# DDR3.net
KiCad netlist of a schematic drawn in Altium Designer
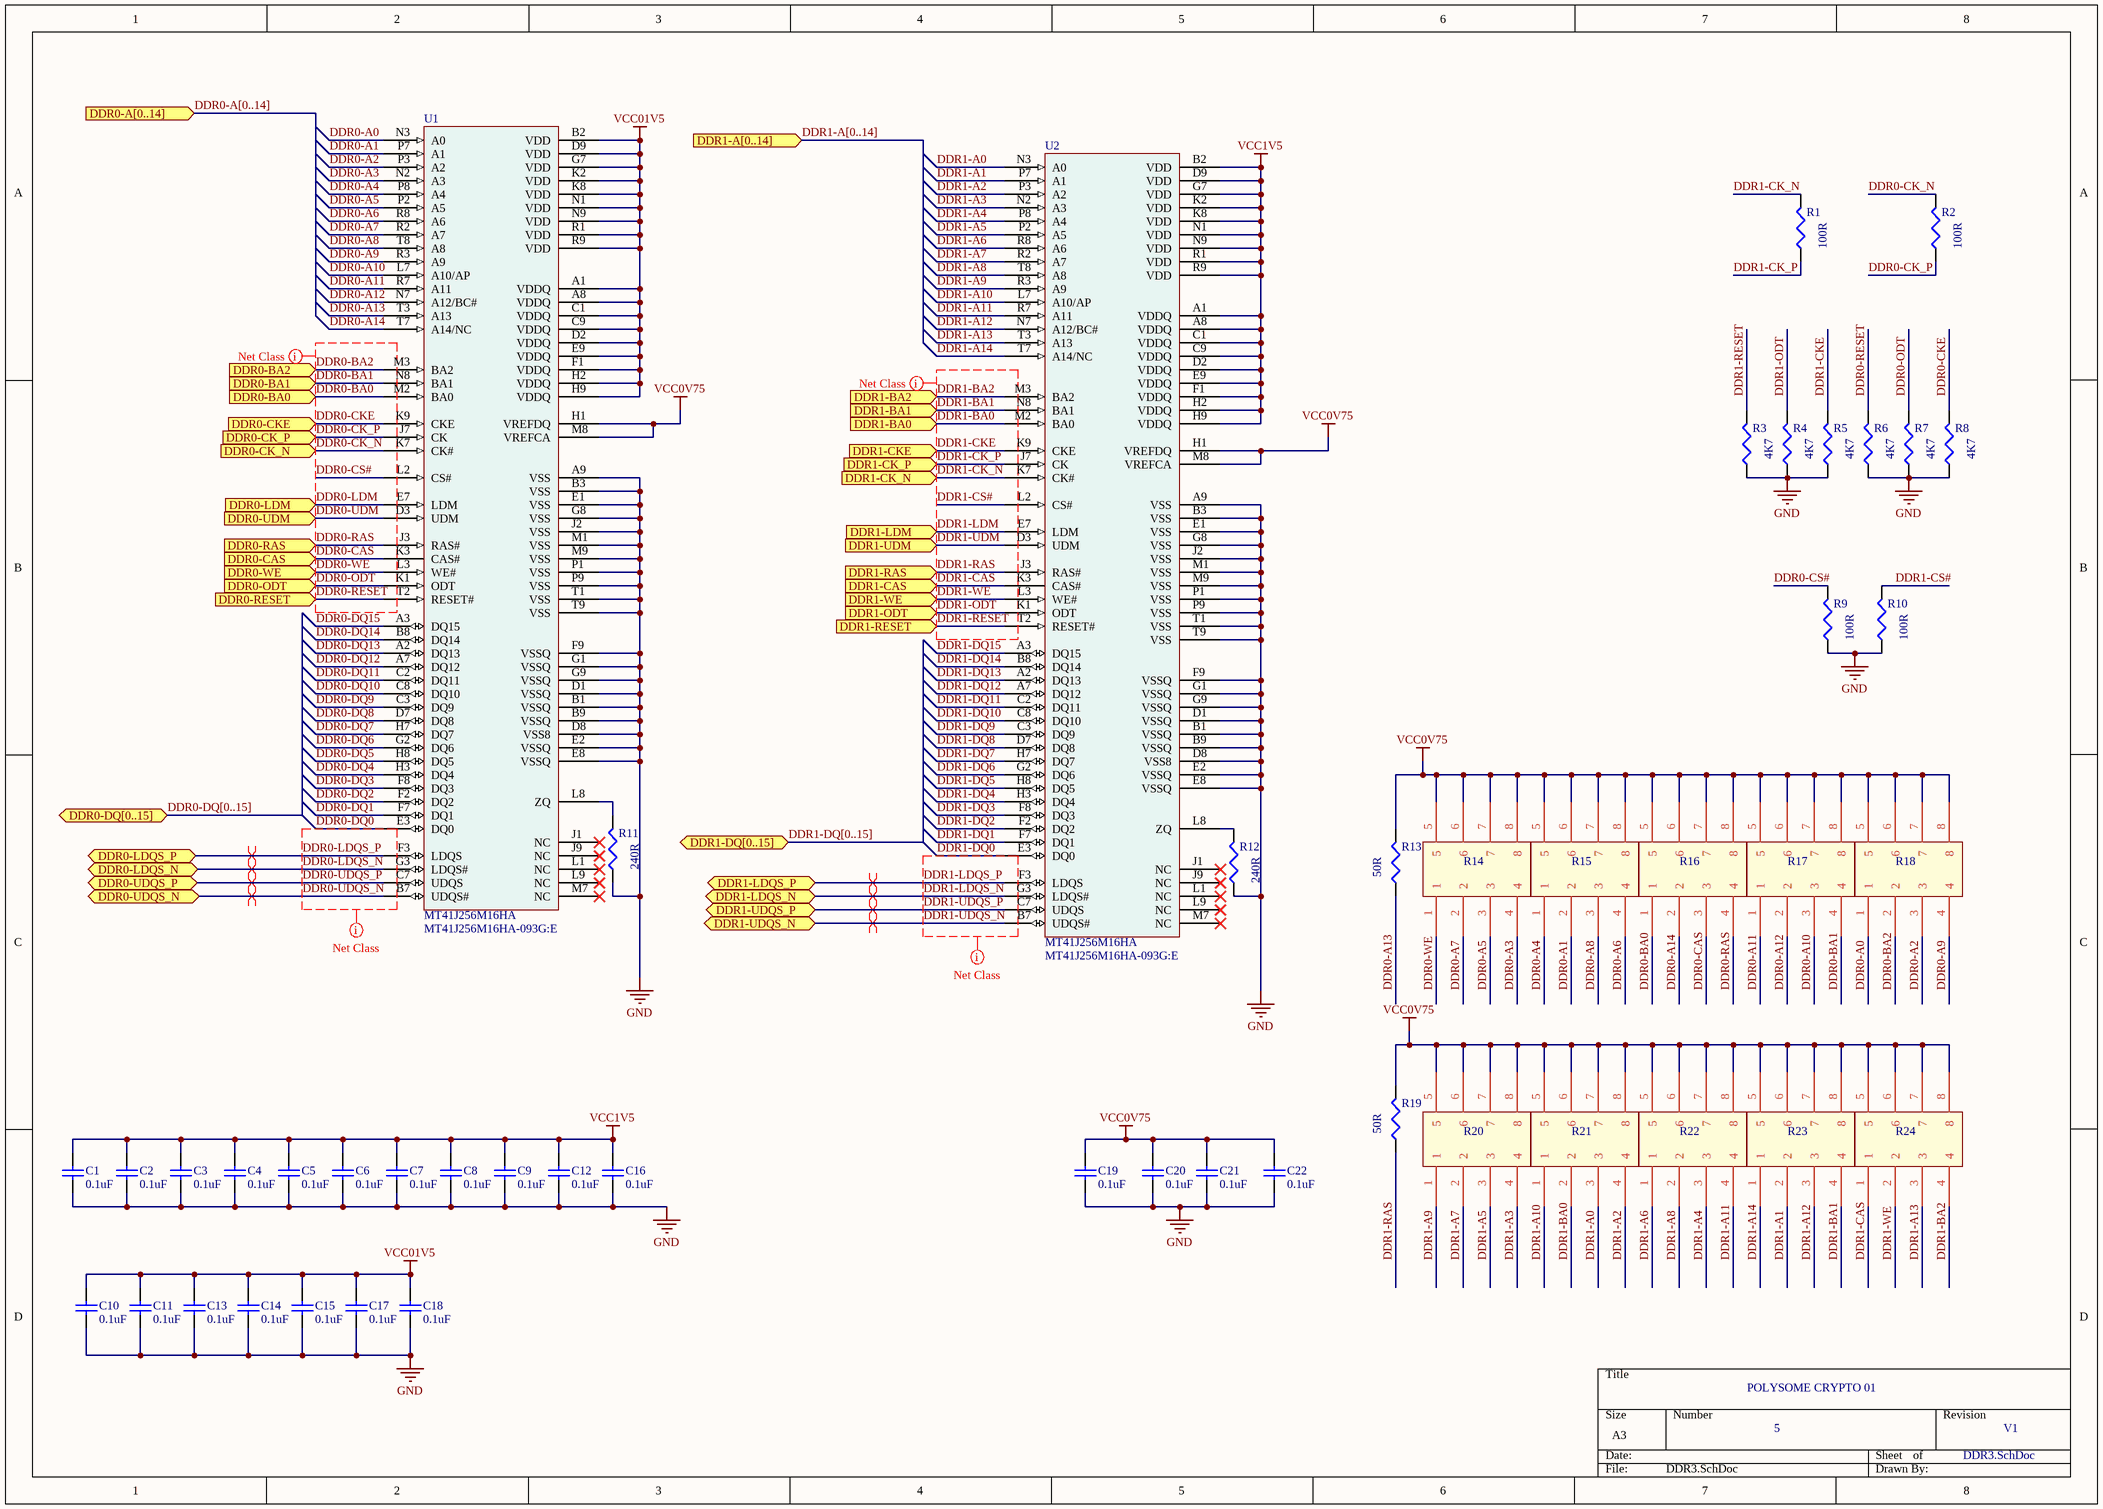
[diagram p0: DDR3.SchDoc]

(export (version "E")
  (design (tool "Eeschema 10.0.6"))
  (components
    (comp (ref "C1")
      (value "0.1uF")
      (footprint "0402")
      (description "Capacitor (Semiconductor SIM Model)")
      (fields (field (name "Comment") "Cap Semi") (field (name "PUBLISHER") "Altium Limited"))
      (libsource (lib "Miscellaneous Devices") (part "Cap Semi"))
    )
    (comp (ref "C2")
      (value "0.1uF")
      (footprint "0402")
      (description "Capacitor (Semiconductor SIM Model)")
      (fields (field (name "Comment") "Cap Semi") (field (name "PUBLISHER") "Altium Limited"))
      (libsource (lib "Miscellaneous Devices") (part "Cap Semi"))
    )
    (comp (ref "C3")
      (value "0.1uF")
      (footprint "0402")
      (description "Capacitor (Semiconductor SIM Model)")
      (fields (field (name "Comment") "Cap Semi") (field (name "PUBLISHER") "Altium Limited"))
      (libsource (lib "Miscellaneous Devices") (part "Cap Semi"))
    )
    (comp (ref "C4")
      (value "0.1uF")
      (footprint "0402")
      (description "Capacitor (Semiconductor SIM Model)")
      (fields (field (name "Comment") "Cap Semi") (field (name "PUBLISHER") "Altium Limited"))
      (libsource (lib "Miscellaneous Devices") (part "Cap Semi"))
    )
    (comp (ref "C5")
      (value "0.1uF")
      (footprint "0402")
      (description "Capacitor (Semiconductor SIM Model)")
      (fields (field (name "Comment") "Cap Semi") (field (name "PUBLISHER") "Altium Limited"))
      (libsource (lib "Miscellaneous Devices") (part "Cap Semi"))
    )
    (comp (ref "C6")
      (value "0.1uF")
      (footprint "0402")
      (description "Capacitor (Semiconductor SIM Model)")
      (fields (field (name "Comment") "Cap Semi") (field (name "PUBLISHER") "Altium Limited"))
      (libsource (lib "Miscellaneous Devices") (part "Cap Semi"))
    )
    (comp (ref "C7")
      (value "0.1uF")
      (footprint "0402")
      (description "Capacitor (Semiconductor SIM Model)")
      (fields (field (name "Comment") "Cap Semi") (field (name "PUBLISHER") "Altium Limited"))
      (libsource (lib "Miscellaneous Devices") (part "Cap Semi"))
    )
    (comp (ref "C8")
      (value "0.1uF")
      (footprint "0402")
      (description "Capacitor (Semiconductor SIM Model)")
      (fields (field (name "Comment") "Cap Semi") (field (name "PUBLISHER") "Altium Limited"))
      (libsource (lib "Miscellaneous Devices") (part "Cap Semi"))
    )
    (comp (ref "C9")
      (value "0.1uF")
      (footprint "0402")
      (description "Capacitor (Semiconductor SIM Model)")
      (fields (field (name "Comment") "Cap Semi") (field (name "PUBLISHER") "Altium Limited"))
      (libsource (lib "Miscellaneous Devices") (part "Cap Semi"))
    )
    (comp (ref "C10")
      (value "0.1uF")
      (footprint "0402")
      (description "Capacitor (Semiconductor SIM Model)")
      (fields (field (name "Comment") "Cap Semi") (field (name "PUBLISHER") "Altium Limited"))
      (libsource (lib "Miscellaneous Devices") (part "Cap Semi"))
    )
    (comp (ref "C11")
      (value "0.1uF")
      (footprint "0402")
      (description "Capacitor (Semiconductor SIM Model)")
      (fields (field (name "Comment") "Cap Semi") (field (name "PUBLISHER") "Altium Limited"))
      (libsource (lib "Miscellaneous Devices") (part "Cap Semi"))
    )
    (comp (ref "C12")
      (value "0.1uF")
      (footprint "0402")
      (description "Capacitor (Semiconductor SIM Model)")
      (fields (field (name "Comment") "Cap Semi") (field (name "PUBLISHER") "Altium Limited"))
      (libsource (lib "Miscellaneous Devices") (part "Cap Semi"))
    )
    (comp (ref "C13")
      (value "0.1uF")
      (footprint "0402")
      (description "Capacitor (Semiconductor SIM Model)")
      (fields (field (name "Comment") "Cap Semi") (field (name "PUBLISHER") "Altium Limited"))
      (libsource (lib "Miscellaneous Devices") (part "Cap Semi"))
    )
    (comp (ref "C14")
      (value "0.1uF")
      (footprint "0402")
      (description "Capacitor (Semiconductor SIM Model)")
      (fields (field (name "Comment") "Cap Semi") (field (name "PUBLISHER") "Altium Limited"))
      (libsource (lib "Miscellaneous Devices") (part "Cap Semi"))
    )
    (comp (ref "C15")
      (value "0.1uF")
      (footprint "0402")
      (description "Capacitor (Semiconductor SIM Model)")
      (fields (field (name "Comment") "Cap Semi") (field (name "PUBLISHER") "Altium Limited"))
      (libsource (lib "Miscellaneous Devices") (part "Cap Semi"))
    )
    (comp (ref "C16")
      (value "0.1uF")
      (footprint "0402")
      (description "Capacitor (Semiconductor SIM Model)")
      (fields (field (name "Comment") "Cap Semi") (field (name "PUBLISHER") "Altium Limited"))
      (libsource (lib "Miscellaneous Devices") (part "Cap Semi"))
    )
    (comp (ref "C17")
      (value "0.1uF")
      (footprint "0402")
      (description "Capacitor (Semiconductor SIM Model)")
      (fields (field (name "Comment") "Cap Semi") (field (name "PUBLISHER") "Altium Limited"))
      (libsource (lib "Miscellaneous Devices") (part "Cap Semi"))
    )
    (comp (ref "C18")
      (value "0.1uF")
      (footprint "0402")
      (description "Capacitor (Semiconductor SIM Model)")
      (fields (field (name "Comment") "Cap Semi") (field (name "PUBLISHER") "Altium Limited"))
      (libsource (lib "Miscellaneous Devices") (part "Cap Semi"))
    )
    (comp (ref "C19")
      (value "0.1uF")
      (footprint "0402")
      (description "Capacitor (Semiconductor SIM Model)")
      (fields (field (name "Comment") "Cap Semi") (field (name "PUBLISHER") "Altium Limited"))
      (libsource (lib "Miscellaneous Devices") (part "Cap Semi"))
    )
    (comp (ref "C20")
      (value "0.1uF")
      (footprint "0402")
      (description "Capacitor (Semiconductor SIM Model)")
      (fields (field (name "Comment") "Cap Semi") (field (name "PUBLISHER") "Altium Limited"))
      (libsource (lib "Miscellaneous Devices") (part "Cap Semi"))
    )
    (comp (ref "C21")
      (value "0.1uF")
      (footprint "0402")
      (description "Capacitor (Semiconductor SIM Model)")
      (fields (field (name "Comment") "Cap Semi") (field (name "PUBLISHER") "Altium Limited"))
      (libsource (lib "Miscellaneous Devices") (part "Cap Semi"))
    )
    (comp (ref "C22")
      (value "0.1uF")
      (footprint "0402")
      (description "Capacitor (Semiconductor SIM Model)")
      (fields (field (name "Comment") "Cap Semi") (field (name "PUBLISHER") "Altium Limited"))
      (libsource (lib "Miscellaneous Devices") (part "Cap Semi"))
    )
    (comp (ref "R1")
      (value "100R")
      (footprint "0402")
      (description "Resistor")
      (fields (field (name "Comment") "Res3") (field (name "PUBLISHER") "Altium Limited"))
      (libsource (lib "Miscellaneous Devices") (part "Res3"))
    )
    (comp (ref "R2")
      (value "100R")
      (footprint "0402")
      (description "Resistor")
      (fields (field (name "Comment") "Res3") (field (name "PUBLISHER") "Altium Limited"))
      (libsource (lib "Miscellaneous Devices") (part "Res3"))
    )
    (comp (ref "R3")
      (value "4K7")
      (footprint "0402")
      (description "Resistor")
      (fields (field (name "Comment") "Res3") (field (name "PUBLISHER") "Altium Limited"))
      (libsource (lib "Miscellaneous Devices") (part "Res3"))
    )
    (comp (ref "R4")
      (value "4K7")
      (footprint "0402")
      (description "Resistor")
      (fields (field (name "Comment") "Res3") (field (name "PUBLISHER") "Altium Limited"))
      (libsource (lib "Miscellaneous Devices") (part "Res3"))
    )
    (comp (ref "R5")
      (value "4K7")
      (footprint "0402")
      (description "Resistor")
      (fields (field (name "Comment") "Res3") (field (name "PUBLISHER") "Altium Limited"))
      (libsource (lib "Miscellaneous Devices") (part "Res3"))
    )
    (comp (ref "R6")
      (value "4K7")
      (footprint "0402")
      (description "Resistor")
      (fields (field (name "Comment") "Res3") (field (name "PUBLISHER") "Altium Limited"))
      (libsource (lib "Miscellaneous Devices") (part "Res3"))
    )
    (comp (ref "R7")
      (value "4K7")
      (footprint "0402")
      (description "Resistor")
      (fields (field (name "Comment") "Res3") (field (name "PUBLISHER") "Altium Limited"))
      (libsource (lib "Miscellaneous Devices") (part "Res3"))
    )
    (comp (ref "R8")
      (value "4K7")
      (footprint "0402")
      (description "Resistor")
      (fields (field (name "Comment") "Res3") (field (name "PUBLISHER") "Altium Limited"))
      (libsource (lib "Miscellaneous Devices") (part "Res3"))
    )
    (comp (ref "R9")
      (value "100R")
      (footprint "0402")
      (description "Resistor")
      (fields (field (name "Comment") "Res3") (field (name "PUBLISHER") "Altium Limited"))
      (libsource (lib "Miscellaneous Devices") (part "Res3"))
    )
    (comp (ref "R10")
      (value "100R")
      (footprint "0402")
      (description "Resistor")
      (fields (field (name "Comment") "Res3") (field (name "PUBLISHER") "Altium Limited"))
      (libsource (lib "Miscellaneous Devices") (part "Res3"))
    )
    (comp (ref "R11")
      (value "240R")
      (footprint "0402")
      (description "Resistor")
      (fields (field (name "Comment") "Res3") (field (name "PUBLISHER") "Altium Limited"))
      (libsource (lib "Miscellaneous Devices") (part "Res3"))
    )
    (comp (ref "R12")
      (value "240R")
      (footprint "0402")
      (description "Resistor")
      (fields (field (name "Comment") "Res3") (field (name "PUBLISHER") "Altium Limited"))
      (libsource (lib "Miscellaneous Devices") (part "Res3"))
    )
    (comp (ref "R13")
      (value "50R")
      (footprint "0402")
      (description "Resistor")
      (fields (field (name "Comment") "Res3") (field (name "PUBLISHER") "Altium Limited"))
      (libsource (lib "Miscellaneous Devices") (part "Res3"))
    )
    (comp (ref "R14")
      (value "RES_4_PACK")
      (footprint "YC124-FR-0749R9L")
      (description "Resistor Networks & Arrays 49.9 Ohm 1% 1/16W 50 Volts")
      (fields
        (field (name "MANUFACTURER") "Yageo")
        (field (name "MANUFACTURER PART NUMBER") "YC124-FR-0749R9L")
      )
      (libsource (lib "PolySomeCrypto01") (part "YC124-FR-0749R9L"))
    )
    (comp (ref "R15")
      (value "RES_4_PACK")
      (footprint "YC124-FR-0749R9L")
      (description "Resistor Networks & Arrays 49.9 Ohm 1% 1/16W 50 Volts")
      (fields
        (field (name "MANUFACTURER") "Yageo")
        (field (name "MANUFACTURER PART NUMBER") "YC124-FR-0749R9L")
      )
      (libsource (lib "PolySomeCrypto01") (part "YC124-FR-0749R9L"))
    )
    (comp (ref "R16")
      (value "RES_4_PACK")
      (footprint "YC124-FR-0749R9L")
      (description "Resistor Networks & Arrays 49.9 Ohm 1% 1/16W 50 Volts")
      (fields
        (field (name "MANUFACTURER") "Yageo")
        (field (name "MANUFACTURER PART NUMBER") "YC124-FR-0749R9L")
      )
      (libsource (lib "PolySomeCrypto01") (part "YC124-FR-0749R9L"))
    )
    (comp (ref "R17")
      (value "RES_4_PACK")
      (footprint "YC124-FR-0749R9L")
      (description "Resistor Networks & Arrays 49.9 Ohm 1% 1/16W 50 Volts")
      (fields
        (field (name "MANUFACTURER") "Yageo")
        (field (name "MANUFACTURER PART NUMBER") "YC124-FR-0749R9L")
      )
      (libsource (lib "PolySomeCrypto01") (part "YC124-FR-0749R9L"))
    )
    (comp (ref "R18")
      (value "RES_4_PACK")
      (footprint "YC124-FR-0749R9L")
      (description "Resistor Networks & Arrays 49.9 Ohm 1% 1/16W 50 Volts")
      (fields
        (field (name "MANUFACTURER") "Yageo")
        (field (name "MANUFACTURER PART NUMBER") "YC124-FR-0749R9L")
      )
      (libsource (lib "PolySomeCrypto01") (part "YC124-FR-0749R9L"))
    )
    (comp (ref "R19")
      (value "50R")
      (footprint "0402")
      (description "Resistor")
      (fields (field (name "Comment") "Res3") (field (name "PUBLISHER") "Altium Limited"))
      (libsource (lib "Miscellaneous Devices") (part "Res3"))
    )
    (comp (ref "R20")
      (value "RES_4_PACK")
      (footprint "YC124-FR-0749R9L")
      (description "Resistor Networks & Arrays 49.9 Ohm 1% 1/16W 50 Volts")
      (fields
        (field (name "MANUFACTURER") "Yageo")
        (field (name "MANUFACTURER PART NUMBER") "YC124-FR-0749R9L")
      )
      (libsource (lib "PolySomeCrypto01") (part "YC124-FR-0749R9L"))
    )
    (comp (ref "R21")
      (value "RES_4_PACK")
      (footprint "YC124-FR-0749R9L")
      (description "Resistor Networks & Arrays 49.9 Ohm 1% 1/16W 50 Volts")
      (fields
        (field (name "MANUFACTURER") "Yageo")
        (field (name "MANUFACTURER PART NUMBER") "YC124-FR-0749R9L")
      )
      (libsource (lib "PolySomeCrypto01") (part "YC124-FR-0749R9L"))
    )
    (comp (ref "R22")
      (value "RES_4_PACK")
      (footprint "YC124-FR-0749R9L")
      (description "Resistor Networks & Arrays 49.9 Ohm 1% 1/16W 50 Volts")
      (fields
        (field (name "MANUFACTURER") "Yageo")
        (field (name "MANUFACTURER PART NUMBER") "YC124-FR-0749R9L")
      )
      (libsource (lib "PolySomeCrypto01") (part "YC124-FR-0749R9L"))
    )
    (comp (ref "R23")
      (value "RES_4_PACK")
      (footprint "YC124-FR-0749R9L")
      (description "Resistor Networks & Arrays 49.9 Ohm 1% 1/16W 50 Volts")
      (fields
        (field (name "MANUFACTURER") "Yageo")
        (field (name "MANUFACTURER PART NUMBER") "YC124-FR-0749R9L")
      )
      (libsource (lib "PolySomeCrypto01") (part "YC124-FR-0749R9L"))
    )
    (comp (ref "R24")
      (value "RES_4_PACK")
      (footprint "YC124-FR-0749R9L")
      (description "Resistor Networks & Arrays 49.9 Ohm 1% 1/16W 50 Volts")
      (fields
        (field (name "MANUFACTURER") "Yageo")
        (field (name "MANUFACTURER PART NUMBER") "YC124-FR-0749R9L")
      )
      (libsource (lib "PolySomeCrypto01") (part "YC124-FR-0749R9L"))
    )
    (comp (ref "U1")
      (value "MT41J256M16HA")
      (description "IC DDR3 SDRAM 4GBIT FBGA")
      (fields
        (field (name "MANUFACTURER") "Micron Technology Inc")
        (field (name "MANUFACTURER PART NUMBER") "MT41J256M16HA-093G:E")
      )
      (libsource (lib "PolySomeCrypto01") (part "MT41J256M16HA-093G{colon}E"))
    )
    (comp (ref "U2")
      (value "MT41J256M16HA")
      (description "IC DDR3 SDRAM 4GBIT FBGA")
      (fields
        (field (name "MANUFACTURER") "Micron Technology Inc")
        (field (name "MANUFACTURER PART NUMBER") "MT41J256M16HA-093G:E")
      )
      (libsource (lib "PolySomeCrypto01") (part "MT41J256M16HA-093G{colon}E"))
    )
  )
  (nets
    (net (code "1") (name "/DDR0-A0") (class "Default")
      (node (ref "R18") (pin "1") (pinfunction "1_1") (pintype "passive"))
      (node (ref "U1") (pin "N3") (pinfunction "A0_N3") (pintype "input"))
    )
    (net (code "2") (name "/DDR0-A1") (class "Default")
      (node (ref "R15") (pin "2") (pinfunction "2_2") (pintype "passive"))
      (node (ref "U1") (pin "P7") (pinfunction "A1_P7") (pintype "input"))
    )
    (net (code "3") (name "/DDR0-A2") (class "Default")
      (node (ref "R18") (pin "3") (pinfunction "3_3") (pintype "passive"))
      (node (ref "U1") (pin "P3") (pinfunction "A2_P3") (pintype "input"))
    )
    (net (code "4") (name "/DDR0-A3") (class "Default")
      (node (ref "R14") (pin "4") (pinfunction "4_4") (pintype "passive"))
      (node (ref "U1") (pin "N2") (pinfunction "A3_N2") (pintype "input"))
    )
    (net (code "5") (name "/DDR0-A4") (class "Default")
      (node (ref "R15") (pin "1") (pinfunction "1_1") (pintype "passive"))
      (node (ref "U1") (pin "P8") (pinfunction "A4_P8") (pintype "input"))
    )
    (net (code "6") (name "/DDR0-A5") (class "Default")
      (node (ref "R14") (pin "3") (pinfunction "3_3") (pintype "passive"))
      (node (ref "U1") (pin "P2") (pinfunction "A5_P2") (pintype "input"))
    )
    (net (code "7") (name "/DDR0-A6") (class "Default")
      (node (ref "R15") (pin "4") (pinfunction "4_4") (pintype "passive"))
      (node (ref "U1") (pin "R8") (pinfunction "A6_R8") (pintype "input"))
    )
    (net (code "8") (name "/DDR0-A7") (class "Default")
      (node (ref "R14") (pin "2") (pinfunction "2_2") (pintype "passive"))
      (node (ref "U1") (pin "R2") (pinfunction "A7_R2") (pintype "input"))
    )
    (net (code "9") (name "/DDR0-A8") (class "Default")
      (node (ref "R15") (pin "3") (pinfunction "3_3") (pintype "passive"))
      (node (ref "U1") (pin "T8") (pinfunction "A8_T8") (pintype "input"))
    )
    (net (code "10") (name "/DDR0-A9") (class "Default")
      (node (ref "R18") (pin "4") (pinfunction "4_4") (pintype "passive"))
      (node (ref "U1") (pin "R3") (pinfunction "A9_R3") (pintype "input"))
    )
    (net (code "11") (name "/DDR0-A10") (class "Default")
      (node (ref "R17") (pin "3") (pinfunction "3_3") (pintype "passive"))
      (node (ref "U1") (pin "L7") (pinfunction "A10/AP_L7") (pintype "input"))
    )
    (net (code "12") (name "/DDR0-A11") (class "Default")
      (node (ref "R17") (pin "1") (pinfunction "1_1") (pintype "passive"))
      (node (ref "U1") (pin "R7") (pinfunction "A11_R7") (pintype "input"))
    )
    (net (code "13") (name "/DDR0-A12") (class "Default")
      (node (ref "R17") (pin "2") (pinfunction "2_2") (pintype "passive"))
      (node (ref "U1") (pin "N7") (pinfunction "A12/BC#_N7") (pintype "input"))
    )
    (net (code "14") (name "/DDR0-A13") (class "Default")
      (node (ref "R13") (pin "1") (pinfunction "1_1") (pintype "passive"))
      (node (ref "U1") (pin "T3") (pinfunction "A13_T3") (pintype "input"))
    )
    (net (code "15") (name "/DDR0-A14") (class "Default")
      (node (ref "R16") (pin "2") (pinfunction "2_2") (pintype "passive"))
      (node (ref "U1") (pin "T7") (pinfunction "A14/NC_T7") (pintype "input"))
    )
    (net (code "17") (name "/DDR0-BA0") (class "Default")
      (node (ref "R16") (pin "1") (pinfunction "1_1") (pintype "passive"))
      (node (ref "U1") (pin "M2") (pinfunction "BA0_M2") (pintype "input"))
    )
    (net (code "18") (name "/DDR0-BA1") (class "Default")
      (node (ref "R17") (pin "4") (pinfunction "4_4") (pintype "passive"))
      (node (ref "U1") (pin "N8") (pinfunction "BA1_N8") (pintype "input"))
    )
    (net (code "19") (name "/DDR0-BA2") (class "Default")
      (node (ref "R18") (pin "2") (pinfunction "2_2") (pintype "passive"))
      (node (ref "U1") (pin "M3") (pinfunction "BA2_M3") (pintype "input"))
    )
    (net (code "20") (name "/DDR0-CAS") (class "Default")
      (node (ref "R16") (pin "3") (pinfunction "3_3") (pintype "passive"))
      (node (ref "U1") (pin "K3") (pinfunction "CAS#_K3") (pintype "passive"))
    )
    (net (code "21") (name "/DDR0-CKE") (class "Default")
      (node (ref "R8") (pin "2") (pinfunction "2_2") (pintype "passive"))
      (node (ref "U1") (pin "K9") (pinfunction "CKE_K9") (pintype "input"))
    )
    (net (code "22") (name "/DDR0-CK_N") (class "Default")
      (node (ref "R2") (pin "2") (pinfunction "2_2") (pintype "passive"))
      (node (ref "U1") (pin "K7") (pinfunction "CK#_K7") (pintype "input"))
    )
    (net (code "23") (name "/DDR0-CK_P") (class "Default")
      (node (ref "R2") (pin "1") (pinfunction "1_1") (pintype "passive"))
      (node (ref "U1") (pin "J7") (pinfunction "CK_J7") (pintype "input"))
    )
    (net (code "24") (name "/DDR0-CS#") (class "Default")
      (node (ref "R9") (pin "2") (pinfunction "2_2") (pintype "passive"))
      (node (ref "U1") (pin "L2") (pinfunction "CS#_L2") (pintype "input"))
    )
    (net (code "25") (name "/DDR0-DQ0") (class "Default")
      (node (ref "U1") (pin "E3") (pinfunction "DQ0_E3") (pintype "bidirectional"))
    )
    (net (code "26") (name "/DDR0-DQ1") (class "Default")
      (node (ref "U1") (pin "F7") (pinfunction "DQ1_F7") (pintype "bidirectional"))
    )
    (net (code "27") (name "/DDR0-DQ2") (class "Default")
      (node (ref "U1") (pin "F2") (pinfunction "DQ2_F2") (pintype "bidirectional"))
    )
    (net (code "28") (name "/DDR0-DQ3") (class "Default")
      (node (ref "U1") (pin "F8") (pinfunction "DQ3_F8") (pintype "bidirectional"))
    )
    (net (code "29") (name "/DDR0-DQ4") (class "Default")
      (node (ref "U1") (pin "H3") (pinfunction "DQ4_H3") (pintype "bidirectional"))
    )
    (net (code "30") (name "/DDR0-DQ5") (class "Default")
      (node (ref "U1") (pin "H8") (pinfunction "DQ5_H8") (pintype "bidirectional"))
    )
    (net (code "31") (name "/DDR0-DQ6") (class "Default")
      (node (ref "U1") (pin "G2") (pinfunction "DQ6_G2") (pintype "bidirectional"))
    )
    (net (code "32") (name "/DDR0-DQ7") (class "Default")
      (node (ref "U1") (pin "H7") (pinfunction "DQ7_H7") (pintype "bidirectional"))
    )
    (net (code "33") (name "/DDR0-DQ8") (class "Default")
      (node (ref "U1") (pin "D7") (pinfunction "DQ8_D7") (pintype "bidirectional"))
    )
    (net (code "34") (name "/DDR0-DQ9") (class "Default")
      (node (ref "U1") (pin "C3") (pinfunction "DQ9_C3") (pintype "bidirectional"))
    )
    (net (code "35") (name "/DDR0-DQ10") (class "Default")
      (node (ref "U1") (pin "C8") (pinfunction "DQ10_C8") (pintype "bidirectional"))
    )
    (net (code "36") (name "/DDR0-DQ11") (class "Default")
      (node (ref "U1") (pin "C2") (pinfunction "DQ11_C2") (pintype "bidirectional"))
    )
    (net (code "37") (name "/DDR0-DQ12") (class "Default")
      (node (ref "U1") (pin "A7") (pinfunction "DQ12_A7") (pintype "bidirectional"))
    )
    (net (code "38") (name "/DDR0-DQ13") (class "Default")
      (node (ref "U1") (pin "A2") (pinfunction "DQ13_A2") (pintype "bidirectional"))
    )
    (net (code "39") (name "/DDR0-DQ14") (class "Default")
      (node (ref "U1") (pin "B8") (pinfunction "DQ14_B8") (pintype "bidirectional"))
    )
    (net (code "40") (name "/DDR0-DQ15") (class "Default")
      (node (ref "U1") (pin "A3") (pinfunction "DQ15_A3") (pintype "bidirectional"))
    )
    (net (code "42") (name "/DDR0-LDM") (class "Default")
      (node (ref "U1") (pin "E7") (pinfunction "LDM_E7") (pintype "input"))
    )
    (net (code "43") (name "/DDR0-LDQS_N") (class "Default")
      (node (ref "U1") (pin "G3") (pinfunction "LDQS#_G3") (pintype "bidirectional"))
    )
    (net (code "44") (name "/DDR0-LDQS_P") (class "Default")
      (node (ref "U1") (pin "F3") (pinfunction "LDQS_F3") (pintype "bidirectional"))
    )
    (net (code "45") (name "/DDR0-ODT") (class "Default")
      (node (ref "R7") (pin "2") (pinfunction "2_2") (pintype "passive"))
      (node (ref "U1") (pin "K1") (pinfunction "ODT_K1") (pintype "input"))
    )
    (net (code "46") (name "/DDR0-RAS") (class "Default")
      (node (ref "R16") (pin "4") (pinfunction "4_4") (pintype "passive"))
      (node (ref "U1") (pin "J3") (pinfunction "RAS#_J3") (pintype "input"))
    )
    (net (code "47") (name "/DDR0-RESET") (class "Default")
      (node (ref "R6") (pin "2") (pinfunction "2_2") (pintype "passive"))
      (node (ref "U1") (pin "T2") (pinfunction "RESET#_T2") (pintype "input"))
    )
    (net (code "48") (name "/DDR0-UDM") (class "Default")
      (node (ref "U1") (pin "D3") (pinfunction "UDM_D3") (pintype "input"))
    )
    (net (code "49") (name "/DDR0-UDQS_N") (class "Default")
      (node (ref "U1") (pin "B7") (pinfunction "UDQS#_B7") (pintype "bidirectional"))
    )
    (net (code "50") (name "/DDR0-UDQS_P") (class "Default")
      (node (ref "U1") (pin "C7") (pinfunction "UDQS_C7") (pintype "bidirectional"))
    )
    (net (code "51") (name "/DDR0-WE") (class "Default")
      (node (ref "R14") (pin "1") (pinfunction "1_1") (pintype "passive"))
      (node (ref "U1") (pin "L3") (pinfunction "WE#_L3") (pintype "input"))
    )
    (net (code "52") (name "/DDR1-A0") (class "Default")
      (node (ref "R21") (pin "3") (pinfunction "3_3") (pintype "passive"))
      (node (ref "U2") (pin "N3") (pinfunction "A0_N3") (pintype "input"))
    )
    (net (code "53") (name "/DDR1-A1") (class "Default")
      (node (ref "R23") (pin "2") (pinfunction "2_2") (pintype "passive"))
      (node (ref "U2") (pin "P7") (pinfunction "A1_P7") (pintype "input"))
    )
    (net (code "54") (name "/DDR1-A2") (class "Default")
      (node (ref "R21") (pin "4") (pinfunction "4_4") (pintype "passive"))
      (node (ref "U2") (pin "P3") (pinfunction "A2_P3") (pintype "input"))
    )
    (net (code "55") (name "/DDR1-A3") (class "Default")
      (node (ref "R20") (pin "4") (pinfunction "4_4") (pintype "passive"))
      (node (ref "U2") (pin "N2") (pinfunction "A3_N2") (pintype "input"))
    )
    (net (code "56") (name "/DDR1-A4") (class "Default")
      (node (ref "R22") (pin "3") (pinfunction "3_3") (pintype "passive"))
      (node (ref "U2") (pin "P8") (pinfunction "A4_P8") (pintype "input"))
    )
    (net (code "57") (name "/DDR1-A5") (class "Default")
      (node (ref "R20") (pin "3") (pinfunction "3_3") (pintype "passive"))
      (node (ref "U2") (pin "P2") (pinfunction "A5_P2") (pintype "input"))
    )
    (net (code "58") (name "/DDR1-A6") (class "Default")
      (node (ref "R22") (pin "1") (pinfunction "1_1") (pintype "passive"))
      (node (ref "U2") (pin "R8") (pinfunction "A6_R8") (pintype "input"))
    )
    (net (code "59") (name "/DDR1-A7") (class "Default")
      (node (ref "R20") (pin "2") (pinfunction "2_2") (pintype "passive"))
      (node (ref "U2") (pin "R2") (pinfunction "A7_R2") (pintype "input"))
    )
    (net (code "60") (name "/DDR1-A8") (class "Default")
      (node (ref "R22") (pin "2") (pinfunction "2_2") (pintype "passive"))
      (node (ref "U2") (pin "T8") (pinfunction "A8_T8") (pintype "input"))
    )
    (net (code "61") (name "/DDR1-A9") (class "Default")
      (node (ref "R20") (pin "1") (pinfunction "1_1") (pintype "passive"))
      (node (ref "U2") (pin "R3") (pinfunction "A9_R3") (pintype "input"))
    )
    (net (code "62") (name "/DDR1-A10") (class "Default")
      (node (ref "R21") (pin "1") (pinfunction "1_1") (pintype "passive"))
      (node (ref "U2") (pin "L7") (pinfunction "A10/AP_L7") (pintype "input"))
    )
    (net (code "63") (name "/DDR1-A11") (class "Default")
      (node (ref "R22") (pin "4") (pinfunction "4_4") (pintype "passive"))
      (node (ref "U2") (pin "R7") (pinfunction "A11_R7") (pintype "input"))
    )
    (net (code "64") (name "/DDR1-A12") (class "Default")
      (node (ref "R23") (pin "3") (pinfunction "3_3") (pintype "passive"))
      (node (ref "U2") (pin "N7") (pinfunction "A12/BC#_N7") (pintype "input"))
    )
    (net (code "65") (name "/DDR1-A13") (class "Default")
      (node (ref "R24") (pin "3") (pinfunction "3_3") (pintype "passive"))
      (node (ref "U2") (pin "T3") (pinfunction "A13_T3") (pintype "input"))
    )
    (net (code "66") (name "/DDR1-A14") (class "Default")
      (node (ref "R23") (pin "1") (pinfunction "1_1") (pintype "passive"))
      (node (ref "U2") (pin "T7") (pinfunction "A14/NC_T7") (pintype "input"))
    )
    (net (code "68") (name "/DDR1-BA0") (class "Default")
      (node (ref "R21") (pin "2") (pinfunction "2_2") (pintype "passive"))
      (node (ref "U2") (pin "M2") (pinfunction "BA0_M2") (pintype "input"))
    )
    (net (code "69") (name "/DDR1-BA1") (class "Default")
      (node (ref "R23") (pin "4") (pinfunction "4_4") (pintype "passive"))
      (node (ref "U2") (pin "N8") (pinfunction "BA1_N8") (pintype "input"))
    )
    (net (code "70") (name "/DDR1-BA2") (class "Default")
      (node (ref "R24") (pin "4") (pinfunction "4_4") (pintype "passive"))
      (node (ref "U2") (pin "M3") (pinfunction "BA2_M3") (pintype "input"))
    )
    (net (code "71") (name "/DDR1-CAS") (class "Default")
      (node (ref "R24") (pin "1") (pinfunction "1_1") (pintype "passive"))
      (node (ref "U2") (pin "K3") (pinfunction "CAS#_K3") (pintype "passive"))
    )
    (net (code "72") (name "/DDR1-CKE") (class "Default")
      (node (ref "R5") (pin "2") (pinfunction "2_2") (pintype "passive"))
      (node (ref "U2") (pin "K9") (pinfunction "CKE_K9") (pintype "input"))
    )
    (net (code "73") (name "/DDR1-CK_N") (class "Default")
      (node (ref "R1") (pin "2") (pinfunction "2_2") (pintype "passive"))
      (node (ref "U2") (pin "K7") (pinfunction "CK#_K7") (pintype "input"))
    )
    (net (code "74") (name "/DDR1-CK_P") (class "Default")
      (node (ref "R1") (pin "1") (pinfunction "1_1") (pintype "passive"))
      (node (ref "U2") (pin "J7") (pinfunction "CK_J7") (pintype "input"))
    )
    (net (code "75") (name "/DDR1-CS#") (class "Default")
      (node (ref "R10") (pin "2") (pinfunction "2_2") (pintype "passive"))
      (node (ref "U2") (pin "L2") (pinfunction "CS#_L2") (pintype "input"))
    )
    (net (code "76") (name "/DDR1-DQ0") (class "Default")
      (node (ref "U2") (pin "E3") (pinfunction "DQ0_E3") (pintype "bidirectional"))
    )
    (net (code "77") (name "/DDR1-DQ1") (class "Default")
      (node (ref "U2") (pin "F7") (pinfunction "DQ1_F7") (pintype "bidirectional"))
    )
    (net (code "78") (name "/DDR1-DQ2") (class "Default")
      (node (ref "U2") (pin "F2") (pinfunction "DQ2_F2") (pintype "bidirectional"))
    )
    (net (code "79") (name "/DDR1-DQ3") (class "Default")
      (node (ref "U2") (pin "F8") (pinfunction "DQ3_F8") (pintype "bidirectional"))
    )
    (net (code "80") (name "/DDR1-DQ4") (class "Default")
      (node (ref "U2") (pin "H3") (pinfunction "DQ4_H3") (pintype "bidirectional"))
    )
    (net (code "81") (name "/DDR1-DQ5") (class "Default")
      (node (ref "U2") (pin "H8") (pinfunction "DQ5_H8") (pintype "bidirectional"))
    )
    (net (code "82") (name "/DDR1-DQ6") (class "Default")
      (node (ref "U2") (pin "G2") (pinfunction "DQ6_G2") (pintype "bidirectional"))
    )
    (net (code "83") (name "/DDR1-DQ7") (class "Default")
      (node (ref "U2") (pin "H7") (pinfunction "DQ7_H7") (pintype "bidirectional"))
    )
    (net (code "84") (name "/DDR1-DQ8") (class "Default")
      (node (ref "U2") (pin "D7") (pinfunction "DQ8_D7") (pintype "bidirectional"))
    )
    (net (code "85") (name "/DDR1-DQ9") (class "Default")
      (node (ref "U2") (pin "C3") (pinfunction "DQ9_C3") (pintype "bidirectional"))
    )
    (net (code "86") (name "/DDR1-DQ10") (class "Default")
      (node (ref "U2") (pin "C8") (pinfunction "DQ10_C8") (pintype "bidirectional"))
    )
    (net (code "87") (name "/DDR1-DQ11") (class "Default")
      (node (ref "U2") (pin "C2") (pinfunction "DQ11_C2") (pintype "bidirectional"))
    )
    (net (code "88") (name "/DDR1-DQ12") (class "Default")
      (node (ref "U2") (pin "A7") (pinfunction "DQ12_A7") (pintype "bidirectional"))
    )
    (net (code "89") (name "/DDR1-DQ13") (class "Default")
      (node (ref "U2") (pin "A2") (pinfunction "DQ13_A2") (pintype "bidirectional"))
    )
    (net (code "90") (name "/DDR1-DQ14") (class "Default")
      (node (ref "U2") (pin "B8") (pinfunction "DQ14_B8") (pintype "bidirectional"))
    )
    (net (code "91") (name "/DDR1-DQ15") (class "Default")
      (node (ref "U2") (pin "A3") (pinfunction "DQ15_A3") (pintype "bidirectional"))
    )
    (net (code "93") (name "/DDR1-LDM") (class "Default")
      (node (ref "U2") (pin "E7") (pinfunction "LDM_E7") (pintype "input"))
    )
    (net (code "94") (name "/DDR1-LDQS_N") (class "Default")
      (node (ref "U2") (pin "G3") (pinfunction "LDQS#_G3") (pintype "bidirectional"))
    )
    (net (code "95") (name "/DDR1-LDQS_P") (class "Default")
      (node (ref "U2") (pin "F3") (pinfunction "LDQS_F3") (pintype "bidirectional"))
    )
    (net (code "96") (name "/DDR1-ODT") (class "Default")
      (node (ref "R4") (pin "2") (pinfunction "2_2") (pintype "passive"))
      (node (ref "U2") (pin "K1") (pinfunction "ODT_K1") (pintype "input"))
    )
    (net (code "97") (name "/DDR1-RAS") (class "Default")
      (node (ref "R19") (pin "1") (pinfunction "1_1") (pintype "passive"))
      (node (ref "U2") (pin "J3") (pinfunction "RAS#_J3") (pintype "input"))
    )
    (net (code "98") (name "/DDR1-RESET") (class "Default")
      (node (ref "R3") (pin "2") (pinfunction "2_2") (pintype "passive"))
      (node (ref "U2") (pin "T2") (pinfunction "RESET#_T2") (pintype "input"))
    )
    (net (code "99") (name "/DDR1-UDM") (class "Default")
      (node (ref "U2") (pin "D3") (pinfunction "UDM_D3") (pintype "input"))
    )
    (net (code "100") (name "/DDR1-UDQS_N") (class "Default")
      (node (ref "U2") (pin "B7") (pinfunction "UDQS#_B7") (pintype "bidirectional"))
    )
    (net (code "101") (name "/DDR1-UDQS_P") (class "Default")
      (node (ref "U2") (pin "C7") (pinfunction "UDQS_C7") (pintype "bidirectional"))
    )
    (net (code "102") (name "/DDR1-WE") (class "Default")
      (node (ref "R24") (pin "2") (pinfunction "2_2") (pintype "passive"))
      (node (ref "U2") (pin "L3") (pinfunction "WE#_L3") (pintype "input"))
    )
    (net (code "103") (name "GND") (class "Default")
      (node (ref "C1") (pin "1") (pinfunction "1_1") (pintype "passive"))
      (node (ref "C10") (pin "1") (pinfunction "1_1") (pintype "passive"))
      (node (ref "C11") (pin "1") (pinfunction "1_1") (pintype "passive"))
      (node (ref "C12") (pin "1") (pinfunction "1_1") (pintype "passive"))
      (node (ref "C13") (pin "1") (pinfunction "1_1") (pintype "passive"))
      (node (ref "C14") (pin "1") (pinfunction "1_1") (pintype "passive"))
      (node (ref "C15") (pin "1") (pinfunction "1_1") (pintype "passive"))
      (node (ref "C16") (pin "1") (pinfunction "1_1") (pintype "passive"))
      (node (ref "C17") (pin "1") (pinfunction "1_1") (pintype "passive"))
      (node (ref "C18") (pin "1") (pinfunction "1_1") (pintype "passive"))
      (node (ref "C19") (pin "2") (pinfunction "2_2") (pintype "passive"))
      (node (ref "C2") (pin "1") (pinfunction "1_1") (pintype "passive"))
      (node (ref "C20") (pin "1") (pinfunction "1_1") (pintype "passive"))
      (node (ref "C21") (pin "1") (pinfunction "1_1") (pintype "passive"))
      (node (ref "C22") (pin "1") (pinfunction "1_1") (pintype "passive"))
      (node (ref "C3") (pin "1") (pinfunction "1_1") (pintype "passive"))
      (node (ref "C4") (pin "1") (pinfunction "1_1") (pintype "passive"))
      (node (ref "C5") (pin "1") (pinfunction "1_1") (pintype "passive"))
      (node (ref "C6") (pin "1") (pinfunction "1_1") (pintype "passive"))
      (node (ref "C7") (pin "1") (pinfunction "1_1") (pintype "passive"))
      (node (ref "C8") (pin "1") (pinfunction "1_1") (pintype "passive"))
      (node (ref "C9") (pin "1") (pinfunction "1_1") (pintype "passive"))
      (node (ref "R10") (pin "1") (pinfunction "1_1") (pintype "passive"))
      (node (ref "R11") (pin "1") (pinfunction "1_1") (pintype "passive"))
      (node (ref "R12") (pin "1") (pinfunction "1_1") (pintype "passive"))
      (node (ref "R3") (pin "1") (pinfunction "1_1") (pintype "passive"))
      (node (ref "R4") (pin "1") (pinfunction "1_1") (pintype "passive"))
      (node (ref "R5") (pin "1") (pinfunction "1_1") (pintype "passive"))
      (node (ref "R6") (pin "1") (pinfunction "1_1") (pintype "passive"))
      (node (ref "R7") (pin "1") (pinfunction "1_1") (pintype "passive"))
      (node (ref "R8") (pin "1") (pinfunction "1_1") (pintype "passive"))
      (node (ref "R9") (pin "1") (pinfunction "1_1") (pintype "passive"))
      (node (ref "U1") (pin "A9") (pinfunction "VSS_A9") (pintype "power_in"))
      (node (ref "U1") (pin "B1") (pinfunction "VSSQ_B1") (pintype "power_in"))
      (node (ref "U1") (pin "B3") (pinfunction "VSS_B3") (pintype "power_in"))
      (node (ref "U1") (pin "B9") (pinfunction "VSSQ_B9") (pintype "power_in"))
      (node (ref "U1") (pin "D1") (pinfunction "VSSQ_D1") (pintype "power_in"))
      (node (ref "U1") (pin "D8") (pinfunction "VSS8_D8") (pintype "power_in"))
      (node (ref "U1") (pin "E1") (pinfunction "VSS_E1") (pintype "power_in"))
      (node (ref "U1") (pin "E2") (pinfunction "VSSQ_E2") (pintype "power_in"))
      (node (ref "U1") (pin "E8") (pinfunction "VSSQ_E8") (pintype "power_in"))
      (node (ref "U1") (pin "F9") (pinfunction "VSSQ_F9") (pintype "power_in"))
      (node (ref "U1") (pin "G1") (pinfunction "VSSQ_G1") (pintype "power_in"))
      (node (ref "U1") (pin "G8") (pinfunction "VSS_G8") (pintype "power_in"))
      (node (ref "U1") (pin "G9") (pinfunction "VSSQ_G9") (pintype "power_in"))
      (node (ref "U1") (pin "J2") (pinfunction "VSS_J2") (pintype "power_in"))
      (node (ref "U1") (pin "M1") (pinfunction "VSS_M1") (pintype "power_in"))
      (node (ref "U1") (pin "M9") (pinfunction "VSS_M9") (pintype "power_in"))
      (node (ref "U1") (pin "P1") (pinfunction "VSS_P1") (pintype "power_in"))
      (node (ref "U1") (pin "P9") (pinfunction "VSS_P9") (pintype "power_in"))
      (node (ref "U1") (pin "T1") (pinfunction "VSS_T1") (pintype "power_in"))
      (node (ref "U1") (pin "T9") (pinfunction "VSS_T9") (pintype "power_in"))
      (node (ref "U2") (pin "A9") (pinfunction "VSS_A9") (pintype "power_in"))
      (node (ref "U2") (pin "B1") (pinfunction "VSSQ_B1") (pintype "power_in"))
      (node (ref "U2") (pin "B3") (pinfunction "VSS_B3") (pintype "power_in"))
      (node (ref "U2") (pin "B9") (pinfunction "VSSQ_B9") (pintype "power_in"))
      (node (ref "U2") (pin "D1") (pinfunction "VSSQ_D1") (pintype "power_in"))
      (node (ref "U2") (pin "D8") (pinfunction "VSS8_D8") (pintype "power_in"))
      (node (ref "U2") (pin "E1") (pinfunction "VSS_E1") (pintype "power_in"))
      (node (ref "U2") (pin "E2") (pinfunction "VSSQ_E2") (pintype "power_in"))
      (node (ref "U2") (pin "E8") (pinfunction "VSSQ_E8") (pintype "power_in"))
      (node (ref "U2") (pin "F9") (pinfunction "VSSQ_F9") (pintype "power_in"))
      (node (ref "U2") (pin "G1") (pinfunction "VSSQ_G1") (pintype "power_in"))
      (node (ref "U2") (pin "G8") (pinfunction "VSS_G8") (pintype "power_in"))
      (node (ref "U2") (pin "G9") (pinfunction "VSSQ_G9") (pintype "power_in"))
      (node (ref "U2") (pin "J2") (pinfunction "VSS_J2") (pintype "power_in"))
      (node (ref "U2") (pin "M1") (pinfunction "VSS_M1") (pintype "power_in"))
      (node (ref "U2") (pin "M9") (pinfunction "VSS_M9") (pintype "power_in"))
      (node (ref "U2") (pin "P1") (pinfunction "VSS_P1") (pintype "power_in"))
      (node (ref "U2") (pin "P9") (pinfunction "VSS_P9") (pintype "power_in"))
      (node (ref "U2") (pin "T1") (pinfunction "VSS_T1") (pintype "power_in"))
      (node (ref "U2") (pin "T9") (pinfunction "VSS_T9") (pintype "power_in"))
    )
    (net (code "104") (name "Net-(U1-ZQ)") (class "Default")
      (node (ref "R11") (pin "2") (pinfunction "2_2") (pintype "passive"))
      (node (ref "U1") (pin "L8") (pinfunction "ZQ_L8") (pintype "passive"))
    )
    (net (code "105") (name "Net-(U2-ZQ)") (class "Default")
      (node (ref "R12") (pin "2") (pinfunction "2_2") (pintype "passive"))
      (node (ref "U2") (pin "L8") (pinfunction "ZQ_L8") (pintype "passive"))
    )
    (net (code "106") (name "VCC0V75") (class "Default")
      (node (ref "C19") (pin "1") (pinfunction "1_1") (pintype "passive"))
      (node (ref "C20") (pin "2") (pinfunction "2_2") (pintype "passive"))
      (node (ref "C21") (pin "2") (pinfunction "2_2") (pintype "passive"))
      (node (ref "C22") (pin "2") (pinfunction "2_2") (pintype "passive"))
      (node (ref "R13") (pin "2") (pinfunction "2_2") (pintype "passive"))
      (node (ref "R14") (pin "5") (pinfunction "5_5") (pintype "passive"))
      (node (ref "R14") (pin "6") (pinfunction "6_6") (pintype "passive"))
      (node (ref "R14") (pin "7") (pinfunction "7_7") (pintype "passive"))
      (node (ref "R14") (pin "8") (pinfunction "8_8") (pintype "passive"))
      (node (ref "R15") (pin "5") (pinfunction "5_5") (pintype "passive"))
      (node (ref "R15") (pin "6") (pinfunction "6_6") (pintype "passive"))
      (node (ref "R15") (pin "7") (pinfunction "7_7") (pintype "passive"))
      (node (ref "R15") (pin "8") (pinfunction "8_8") (pintype "passive"))
      (node (ref "R16") (pin "5") (pinfunction "5_5") (pintype "passive"))
      (node (ref "R16") (pin "6") (pinfunction "6_6") (pintype "passive"))
      (node (ref "R16") (pin "7") (pinfunction "7_7") (pintype "passive"))
      (node (ref "R16") (pin "8") (pinfunction "8_8") (pintype "passive"))
      (node (ref "R17") (pin "5") (pinfunction "5_5") (pintype "passive"))
      (node (ref "R17") (pin "6") (pinfunction "6_6") (pintype "passive"))
      (node (ref "R17") (pin "7") (pinfunction "7_7") (pintype "passive"))
      (node (ref "R17") (pin "8") (pinfunction "8_8") (pintype "passive"))
      (node (ref "R18") (pin "5") (pinfunction "5_5") (pintype "passive"))
      (node (ref "R18") (pin "6") (pinfunction "6_6") (pintype "passive"))
      (node (ref "R18") (pin "7") (pinfunction "7_7") (pintype "passive"))
      (node (ref "R18") (pin "8") (pinfunction "8_8") (pintype "passive"))
      (node (ref "R19") (pin "2") (pinfunction "2_2") (pintype "passive"))
      (node (ref "R20") (pin "5") (pinfunction "5_5") (pintype "passive"))
      (node (ref "R20") (pin "6") (pinfunction "6_6") (pintype "passive"))
      (node (ref "R20") (pin "7") (pinfunction "7_7") (pintype "passive"))
      (node (ref "R20") (pin "8") (pinfunction "8_8") (pintype "passive"))
      (node (ref "R21") (pin "5") (pinfunction "5_5") (pintype "passive"))
      (node (ref "R21") (pin "6") (pinfunction "6_6") (pintype "passive"))
      (node (ref "R21") (pin "7") (pinfunction "7_7") (pintype "passive"))
      (node (ref "R21") (pin "8") (pinfunction "8_8") (pintype "passive"))
      (node (ref "R22") (pin "5") (pinfunction "5_5") (pintype "passive"))
      (node (ref "R22") (pin "6") (pinfunction "6_6") (pintype "passive"))
      (node (ref "R22") (pin "7") (pinfunction "7_7") (pintype "passive"))
      (node (ref "R22") (pin "8") (pinfunction "8_8") (pintype "passive"))
      (node (ref "R23") (pin "5") (pinfunction "5_5") (pintype "passive"))
      (node (ref "R23") (pin "6") (pinfunction "6_6") (pintype "passive"))
      (node (ref "R23") (pin "7") (pinfunction "7_7") (pintype "passive"))
      (node (ref "R23") (pin "8") (pinfunction "8_8") (pintype "passive"))
      (node (ref "R24") (pin "5") (pinfunction "5_5") (pintype "passive"))
      (node (ref "R24") (pin "6") (pinfunction "6_6") (pintype "passive"))
      (node (ref "R24") (pin "7") (pinfunction "7_7") (pintype "passive"))
      (node (ref "R24") (pin "8") (pinfunction "8_8") (pintype "passive"))
      (node (ref "U1") (pin "H1") (pinfunction "VREFDQ_H1") (pintype "power_in"))
      (node (ref "U1") (pin "M8") (pinfunction "VREFCA_M8") (pintype "power_in"))
      (node (ref "U2") (pin "H1") (pinfunction "VREFDQ_H1") (pintype "power_in"))
      (node (ref "U2") (pin "M8") (pinfunction "VREFCA_M8") (pintype "power_in"))
    )
    (net (code "107") (name "VCC1V5") (class "Default")
      (node (ref "C1") (pin "2") (pinfunction "2_2") (pintype "passive"))
      (node (ref "C12") (pin "2") (pinfunction "2_2") (pintype "passive"))
      (node (ref "C16") (pin "2") (pinfunction "2_2") (pintype "passive"))
      (node (ref "C2") (pin "2") (pinfunction "2_2") (pintype "passive"))
      (node (ref "C3") (pin "2") (pinfunction "2_2") (pintype "passive"))
      (node (ref "C4") (pin "2") (pinfunction "2_2") (pintype "passive"))
      (node (ref "C5") (pin "2") (pinfunction "2_2") (pintype "passive"))
      (node (ref "C6") (pin "2") (pinfunction "2_2") (pintype "passive"))
      (node (ref "C7") (pin "2") (pinfunction "2_2") (pintype "passive"))
      (node (ref "C8") (pin "2") (pinfunction "2_2") (pintype "passive"))
      (node (ref "C9") (pin "2") (pinfunction "2_2") (pintype "passive"))
      (node (ref "U2") (pin "A1") (pinfunction "VDDQ_A1") (pintype "power_in"))
      (node (ref "U2") (pin "A8") (pinfunction "VDDQ_A8") (pintype "power_in"))
      (node (ref "U2") (pin "B2") (pinfunction "VDD_B2") (pintype "power_in"))
      (node (ref "U2") (pin "C1") (pinfunction "VDDQ_C1") (pintype "power_in"))
      (node (ref "U2") (pin "C9") (pinfunction "VDDQ_C9") (pintype "power_in"))
      (node (ref "U2") (pin "D2") (pinfunction "VDDQ_D2") (pintype "power_in"))
      (node (ref "U2") (pin "D9") (pinfunction "VDD_D9") (pintype "power_in"))
      (node (ref "U2") (pin "E9") (pinfunction "VDDQ_E9") (pintype "power_in"))
      (node (ref "U2") (pin "F1") (pinfunction "VDDQ_F1") (pintype "power_in"))
      (node (ref "U2") (pin "G7") (pinfunction "VDD_G7") (pintype "power_in"))
      (node (ref "U2") (pin "H2") (pinfunction "VDDQ_H2") (pintype "power_in"))
      (node (ref "U2") (pin "H9") (pinfunction "VDDQ_H9") (pintype "power_in"))
      (node (ref "U2") (pin "K2") (pinfunction "VDD_K2") (pintype "power_in"))
      (node (ref "U2") (pin "K8") (pinfunction "VDD_K8") (pintype "power_in"))
      (node (ref "U2") (pin "N1") (pinfunction "VDD_N1") (pintype "power_in"))
      (node (ref "U2") (pin "N9") (pinfunction "VDD_N9") (pintype "power_in"))
      (node (ref "U2") (pin "R1") (pinfunction "VDD_R1") (pintype "power_in"))
      (node (ref "U2") (pin "R9") (pinfunction "VDD_R9") (pintype "power_in"))
    )
    (net (code "108") (name "VCC01V5") (class "Default")
      (node (ref "C10") (pin "2") (pinfunction "2_2") (pintype "passive"))
      (node (ref "C11") (pin "2") (pinfunction "2_2") (pintype "passive"))
      (node (ref "C13") (pin "2") (pinfunction "2_2") (pintype "passive"))
      (node (ref "C14") (pin "2") (pinfunction "2_2") (pintype "passive"))
      (node (ref "C15") (pin "2") (pinfunction "2_2") (pintype "passive"))
      (node (ref "C17") (pin "2") (pinfunction "2_2") (pintype "passive"))
      (node (ref "C18") (pin "2") (pinfunction "2_2") (pintype "passive"))
      (node (ref "U1") (pin "A1") (pinfunction "VDDQ_A1") (pintype "power_in"))
      (node (ref "U1") (pin "A8") (pinfunction "VDDQ_A8") (pintype "power_in"))
      (node (ref "U1") (pin "B2") (pinfunction "VDD_B2") (pintype "power_in"))
      (node (ref "U1") (pin "C1") (pinfunction "VDDQ_C1") (pintype "power_in"))
      (node (ref "U1") (pin "C9") (pinfunction "VDDQ_C9") (pintype "power_in"))
      (node (ref "U1") (pin "D2") (pinfunction "VDDQ_D2") (pintype "power_in"))
      (node (ref "U1") (pin "D9") (pinfunction "VDD_D9") (pintype "power_in"))
      (node (ref "U1") (pin "E9") (pinfunction "VDDQ_E9") (pintype "power_in"))
      (node (ref "U1") (pin "F1") (pinfunction "VDDQ_F1") (pintype "power_in"))
      (node (ref "U1") (pin "G7") (pinfunction "VDD_G7") (pintype "power_in"))
      (node (ref "U1") (pin "H2") (pinfunction "VDDQ_H2") (pintype "power_in"))
      (node (ref "U1") (pin "H9") (pinfunction "VDDQ_H9") (pintype "power_in"))
      (node (ref "U1") (pin "K2") (pinfunction "VDD_K2") (pintype "power_in"))
      (node (ref "U1") (pin "K8") (pinfunction "VDD_K8") (pintype "power_in"))
      (node (ref "U1") (pin "N1") (pinfunction "VDD_N1") (pintype "power_in"))
      (node (ref "U1") (pin "N9") (pinfunction "VDD_N9") (pintype "power_in"))
      (node (ref "U1") (pin "R1") (pinfunction "VDD_R1") (pintype "power_in"))
      (node (ref "U1") (pin "R9") (pinfunction "VDD_R9") (pintype "power_in"))
    )
    (net (code "109") (name "unconnected-(U1-NC-PadJ1)") (class "Default")
      (node (ref "U1") (pin "J1") (pinfunction "NC_J1") (pintype "tri_state+no_connect"))
    )
    (net (code "110") (name "unconnected-(U1-NC-PadJ9)") (class "Default")
      (node (ref "U1") (pin "J9") (pinfunction "NC_J9") (pintype "tri_state+no_connect"))
    )
    (net (code "111") (name "unconnected-(U1-NC-PadL1)") (class "Default")
      (node (ref "U1") (pin "L1") (pinfunction "NC_L1") (pintype "tri_state+no_connect"))
    )
    (net (code "112") (name "unconnected-(U1-NC-PadL9)") (class "Default")
      (node (ref "U1") (pin "L9") (pinfunction "NC_L9") (pintype "passive+no_connect"))
    )
    (net (code "113") (name "unconnected-(U1-NC-PadM7)") (class "Default")
      (node (ref "U1") (pin "M7") (pinfunction "NC_M7") (pintype "tri_state+no_connect"))
    )
    (net (code "114") (name "unconnected-(U2-NC-PadJ1)") (class "Default")
      (node (ref "U2") (pin "J1") (pinfunction "NC_J1") (pintype "tri_state+no_connect"))
    )
    (net (code "115") (name "unconnected-(U2-NC-PadJ9)") (class "Default")
      (node (ref "U2") (pin "J9") (pinfunction "NC_J9") (pintype "tri_state+no_connect"))
    )
    (net (code "116") (name "unconnected-(U2-NC-PadL1)") (class "Default")
      (node (ref "U2") (pin "L1") (pinfunction "NC_L1") (pintype "tri_state+no_connect"))
    )
    (net (code "117") (name "unconnected-(U2-NC-PadL9)") (class "Default")
      (node (ref "U2") (pin "L9") (pinfunction "NC_L9") (pintype "passive+no_connect"))
    )
    (net (code "118") (name "unconnected-(U2-NC-PadM7)") (class "Default")
      (node (ref "U2") (pin "M7") (pinfunction "NC_M7") (pintype "tri_state+no_connect"))
    )
  )
)
